# schematic.net
KiCad netlist of a schematic drawn in EasyEDA
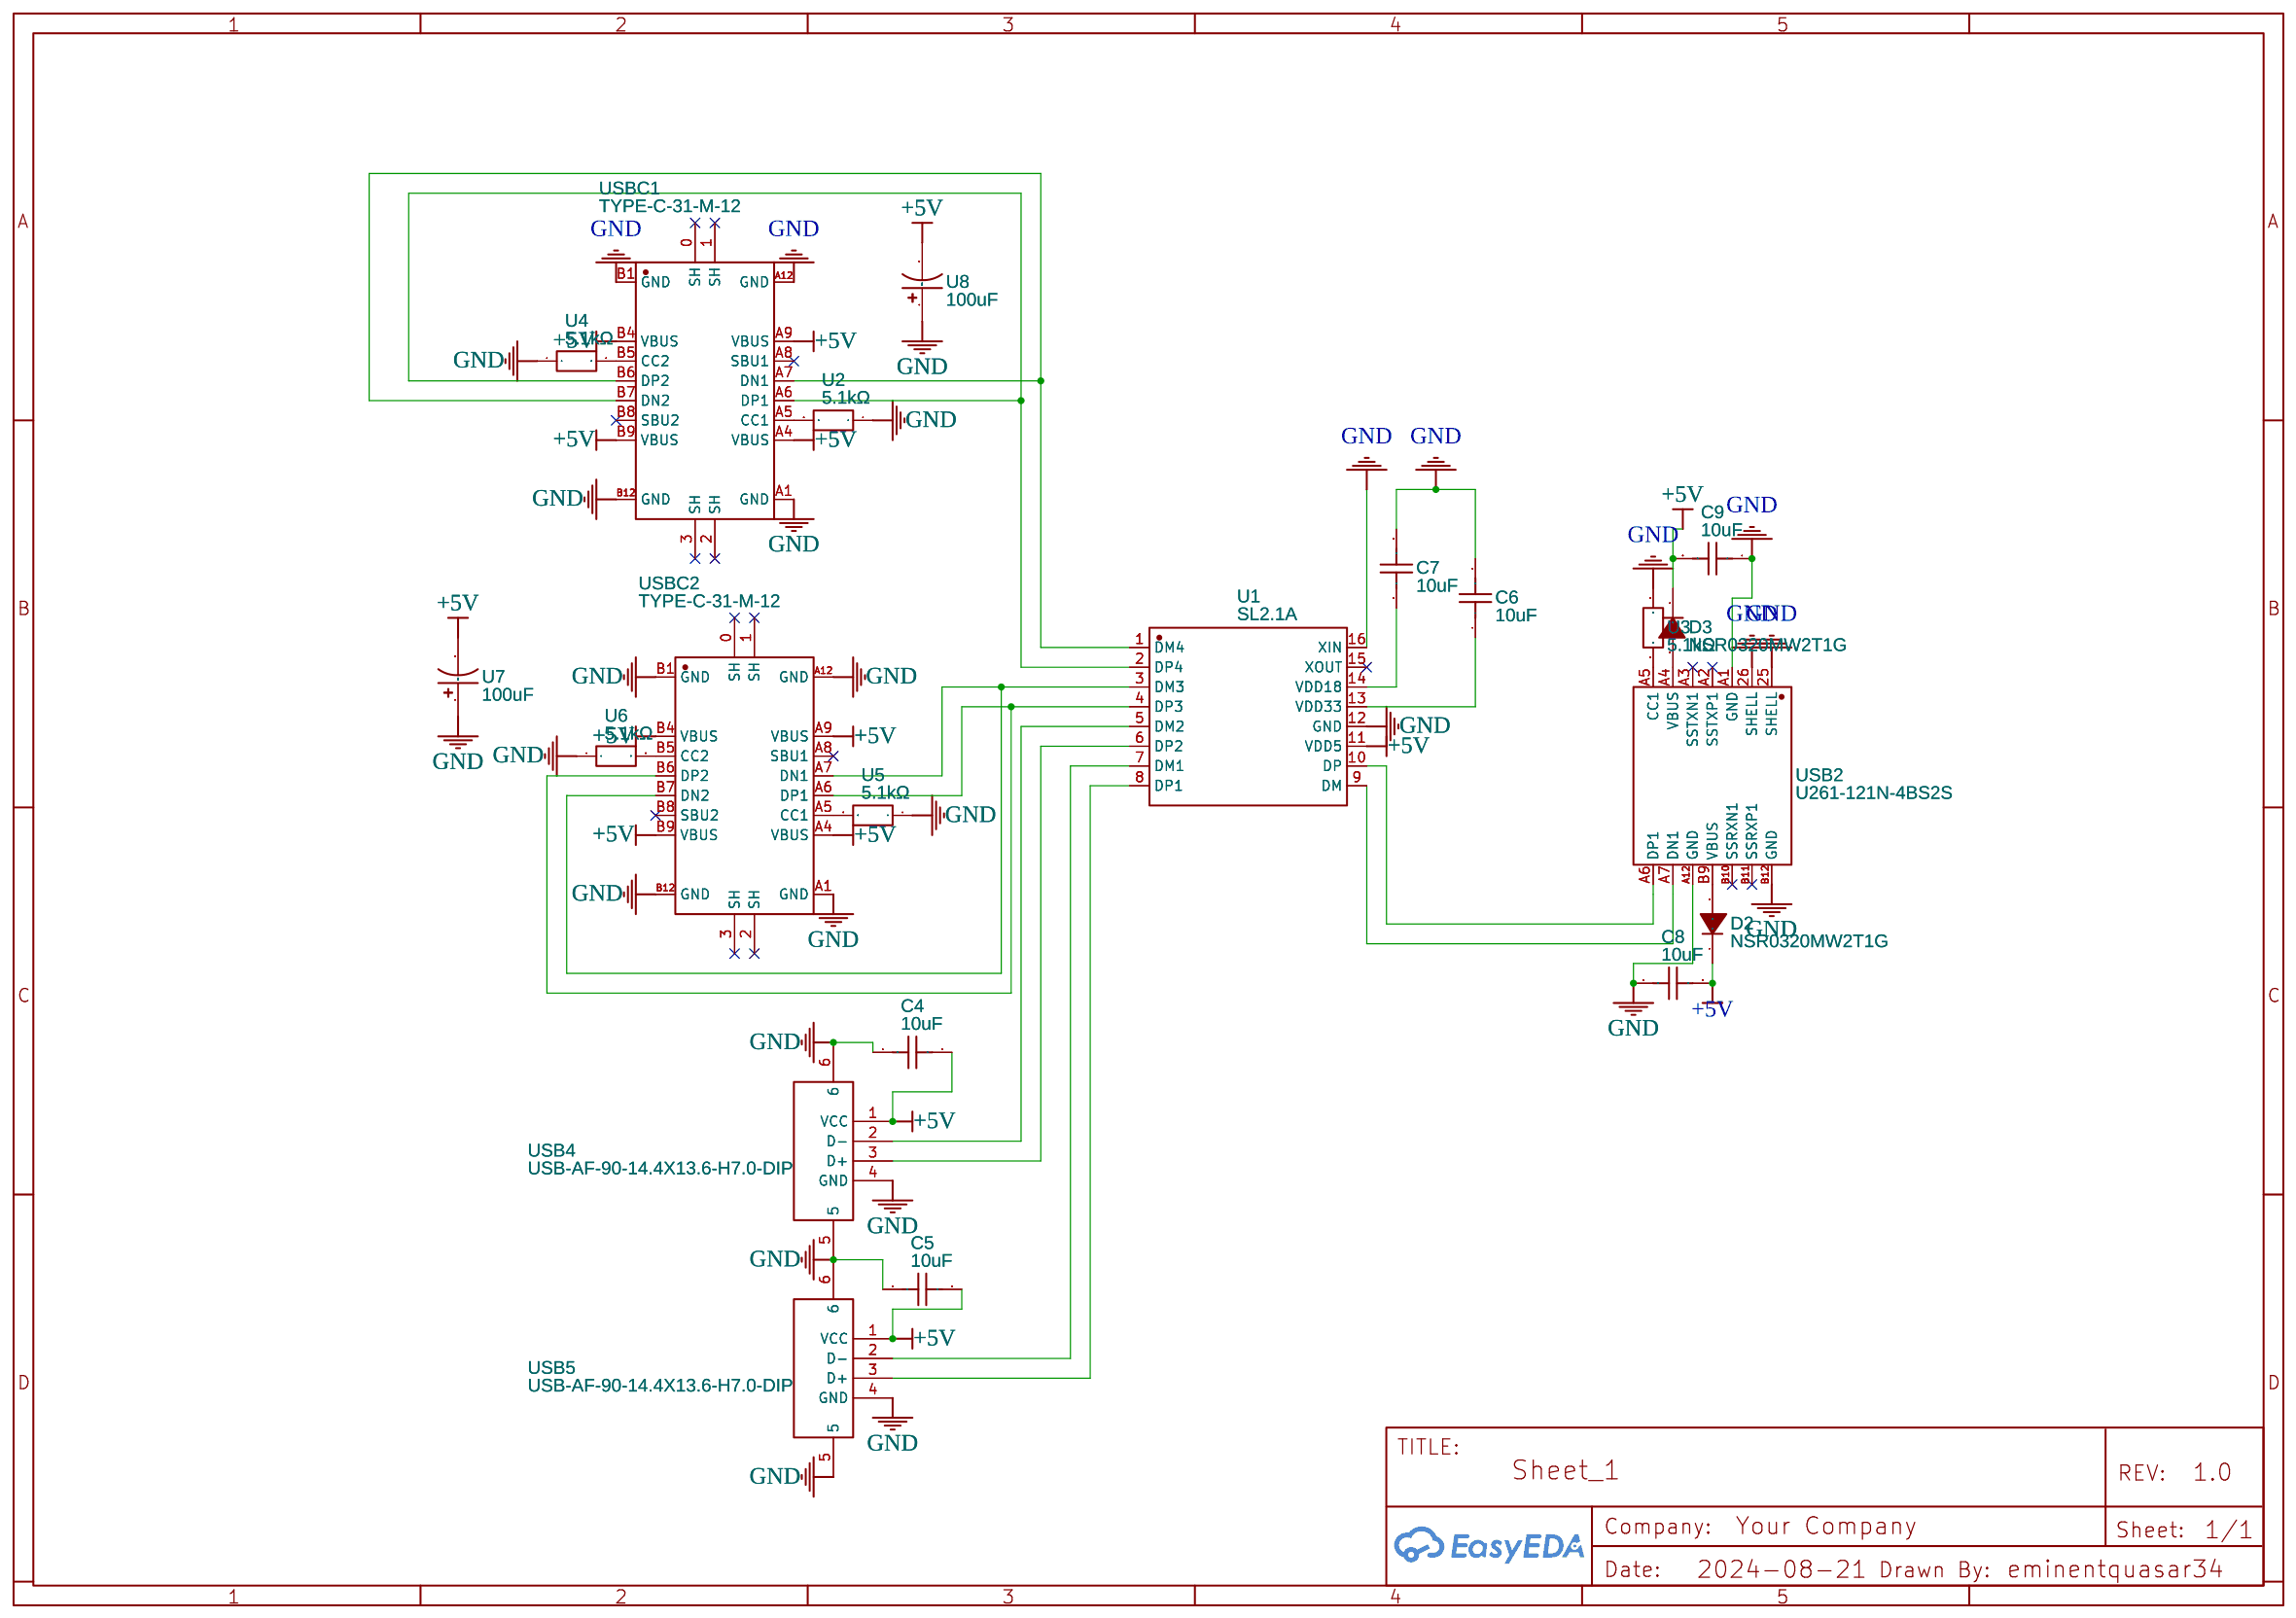
[diagram p0: schematic sheet]

(export (version "E")
  (design (tool "Eeschema 10.0.6"))
  (components
    (comp (ref "C4")
      (value "10uF")
      (fields
        (field (name "Manufacturer Part") "CL10A106KP8NNNC")
        (field (name "Manufacturer") "SAMSUNG(三星)")
      )
      (libsource (lib "") (part "CL10A106KP8NNNC"))
    )
    (comp (ref "C5")
      (value "10uF")
      (fields
        (field (name "Manufacturer Part") "CL10A106KP8NNNC")
        (field (name "Manufacturer") "SAMSUNG(三星)")
      )
      (libsource (lib "") (part "CL10A106KP8NNNC"))
    )
    (comp (ref "C6")
      (value "10uF")
      (fields
        (field (name "Manufacturer Part") "CL10A106KP8NNNC")
        (field (name "Manufacturer") "SAMSUNG(三星)")
      )
      (libsource (lib "") (part "CL10A106KP8NNNC_1"))
    )
    (comp (ref "C7")
      (value "10uF")
      (fields
        (field (name "Manufacturer Part") "CL10A106KP8NNNC")
        (field (name "Manufacturer") "SAMSUNG(三星)")
      )
      (libsource (lib "") (part "CL10A106KP8NNNC_1"))
    )
    (comp (ref "C8")
      (value "10uF")
      (fields
        (field (name "Manufacturer Part") "CL10A106KP8NNNC")
        (field (name "Manufacturer") "SAMSUNG(三星)")
      )
      (libsource (lib "") (part "CL10A106KP8NNNC"))
    )
    (comp (ref "C9")
      (value "10uF")
      (fields
        (field (name "Manufacturer Part") "CL10A106KP8NNNC")
        (field (name "Manufacturer") "SAMSUNG(三星)")
      )
      (libsource (lib "") (part "CL10A106KP8NNNC_2"))
    )
    (comp (ref "D2")
      (value "NSR0320MW2T1G")
      (fields (field (name "Manufacturer") "onsemi(安森美)"))
      (libsource (lib "") (part "NSR0320MW2T1G"))
    )
    (comp (ref "D3")
      (value "NSR0320MW2T1G")
      (fields (field (name "Manufacturer") "onsemi(安森美)"))
      (libsource (lib "") (part "NSR0320MW2T1G_1"))
    )
    (comp (ref "U1")
      (value "SL2.1A")
      (fields (field (name "Manufacturer") "CoreChips(和芯润德)"))
      (libsource (lib "") (part "SL2.1A"))
    )
    (comp (ref "U2")
      (value "5.1kΩ")
      (fields (field (name "Manufacturer Part") "CR1/4W-5K1±5%-ST26") (field (name "Manufacturer") "VO(翔胜)"))
      (libsource (lib "") (part "CR1/4W-5K1±5%-ST26"))
    )
    (comp (ref "U3")
      (value "5.1kΩ")
      (fields (field (name "Manufacturer Part") "CR1/4W-5K1±5%-ST26") (field (name "Manufacturer") "VO(翔胜)"))
      (libsource (lib "") (part "CR1/4W-5K1±5%-ST26_1"))
    )
    (comp (ref "U4")
      (value "5.1kΩ")
      (fields (field (name "Manufacturer Part") "CR1/4W-5K1±5%-ST26") (field (name "Manufacturer") "VO(翔胜)"))
      (libsource (lib "") (part "CR1/4W-5K1±5%-ST26_2"))
    )
    (comp (ref "U5")
      (value "5.1kΩ")
      (fields (field (name "Manufacturer Part") "CR1/4W-5K1±5%-ST26") (field (name "Manufacturer") "VO(翔胜)"))
      (libsource (lib "") (part "CR1/4W-5K1±5%-ST26"))
    )
    (comp (ref "U6")
      (value "5.1kΩ")
      (fields (field (name "Manufacturer Part") "CR1/4W-5K1±5%-ST26") (field (name "Manufacturer") "VO(翔胜)"))
      (libsource (lib "") (part "CR1/4W-5K1±5%-ST26_2"))
    )
    (comp (ref "U7")
      (value "100uF")
      (fields
        (field (name "Manufacturer Part") "16YXF100MEFC6.3X11")
        (field (name "Manufacturer") "rubycon(红宝石)")
      )
      (libsource (lib "") (part "16YXF100MEFC6.3X11"))
    )
    (comp (ref "U8")
      (value "100uF")
      (fields
        (field (name "Manufacturer Part") "16YXF100MEFC6.3X11")
        (field (name "Manufacturer") "rubycon(红宝石)")
      )
      (libsource (lib "") (part "16YXF100MEFC6.3X11_1"))
    )
    (comp (ref "USB2")
      (value "U261-121N-4BS2S")
      (fields (field (name "Manufacturer") "XKB Connectivity(中国星坤)"))
      (libsource (lib "") (part "U261-121N-4BS2S"))
    )
    (comp (ref "USB4")
      (value "USB-AF-90-14.4X13.6-H7.0-DIP")
      (fields (field (name "Manufacturer Part") "903-131A1011D10100") (field (name "Manufacturer") "精拓金"))
      (libsource (lib "") (part "USB-AF-90-14.4X13.6-H7.0-DIP"))
    )
    (comp (ref "USB5")
      (value "USB-AF-90-14.4X13.6-H7.0-DIP")
      (fields (field (name "Manufacturer Part") "903-131A1011D10100") (field (name "Manufacturer") "精拓金"))
      (libsource (lib "") (part "USB-AF-90-14.4X13.6-H7.0-DIP"))
    )
    (comp (ref "USBC1")
      (value "TYPE-C-31-M-12")
      (fields (field (name "Manufacturer") "韩国韩荣"))
      (libsource (lib "") (part "TYPE-C-31-M-12"))
    )
    (comp (ref "USBC2")
      (value "TYPE-C-31-M-12")
      (fields (field (name "Manufacturer") "韩国韩荣"))
      (libsource (lib "") (part "TYPE-C-31-M-12"))
    )
  )
  (nets
    (net (code "1") (name "+5V") (class "Default")
      (node (ref "C4") (pin "2") (pinfunction "2_2") (pintype "unspecified"))
      (node (ref "C5") (pin "2") (pinfunction "2_2") (pintype "unspecified"))
      (node (ref "C8") (pin "2") (pinfunction "2_2") (pintype "unspecified"))
      (node (ref "C9") (pin "2") (pinfunction "2_2") (pintype "unspecified"))
      (node (ref "D2") (pin "1") (pinfunction "C_1") (pintype "unspecified"))
      (node (ref "D3") (pin "1") (pinfunction "C_1") (pintype "unspecified"))
      (node (ref "U1") (pin "11") (pinfunction "VDD5_11") (pintype "unspecified"))
      (node (ref "U7") (pin "2") (pinfunction "2_2") (pintype "unspecified"))
      (node (ref "U8") (pin "2") (pinfunction "2_2") (pintype "unspecified"))
      (node (ref "USB4") (pin "1") (pinfunction "VCC_1") (pintype "unspecified"))
      (node (ref "USB5") (pin "1") (pinfunction "VCC_1") (pintype "unspecified"))
      (node (ref "USBC1") (pin "A4") (pinfunction "VBUS_A4") (pintype "unspecified"))
      (node (ref "USBC1") (pin "A9") (pinfunction "VBUS_A9") (pintype "unspecified"))
      (node (ref "USBC1") (pin "B4") (pinfunction "VBUS_B4") (pintype "unspecified"))
      (node (ref "USBC1") (pin "B9") (pinfunction "VBUS_B9") (pintype "unspecified"))
      (node (ref "USBC2") (pin "A4") (pinfunction "VBUS_A4") (pintype "unspecified"))
      (node (ref "USBC2") (pin "A9") (pinfunction "VBUS_A9") (pintype "unspecified"))
      (node (ref "USBC2") (pin "B4") (pinfunction "VBUS_B4") (pintype "unspecified"))
      (node (ref "USBC2") (pin "B9") (pinfunction "VBUS_B9") (pintype "unspecified"))
    )
    (net (code "2") (name "GND") (class "Default")
      (node (ref "C4") (pin "1") (pinfunction "1_1") (pintype "unspecified"))
      (node (ref "C5") (pin "1") (pinfunction "1_1") (pintype "unspecified"))
      (node (ref "C6") (pin "2") (pinfunction "2_2") (pintype "unspecified"))
      (node (ref "C7") (pin "2") (pinfunction "2_2") (pintype "unspecified"))
      (node (ref "C8") (pin "1") (pinfunction "1_1") (pintype "unspecified"))
      (node (ref "C9") (pin "1") (pinfunction "1_1") (pintype "unspecified"))
      (node (ref "U1") (pin "12") (pinfunction "GND_12") (pintype "unspecified"))
      (node (ref "U1") (pin "16") (pinfunction "XIN_16") (pintype "unspecified"))
      (node (ref "U2") (pin "1") (pinfunction "1_1") (pintype "unspecified"))
      (node (ref "U3") (pin "2") (pinfunction "2_2") (pintype "unspecified"))
      (node (ref "U4") (pin "1") (pinfunction "1_1") (pintype "unspecified"))
      (node (ref "U5") (pin "1") (pinfunction "1_1") (pintype "unspecified"))
      (node (ref "U6") (pin "1") (pinfunction "1_1") (pintype "unspecified"))
      (node (ref "U7") (pin "1") (pinfunction "1_1") (pintype "unspecified"))
      (node (ref "U8") (pin "1") (pinfunction "1_1") (pintype "unspecified"))
      (node (ref "USB2") (pin "25") (pinfunction "SHELL_25") (pintype "unspecified"))
      (node (ref "USB2") (pin "26") (pinfunction "SHELL_26") (pintype "unspecified"))
      (node (ref "USB2") (pin "A1") (pinfunction "GND_A1") (pintype "unspecified"))
      (node (ref "USB2") (pin "A12") (pinfunction "GND_A12") (pintype "unspecified"))
      (node (ref "USB2") (pin "B12") (pinfunction "GND_B12") (pintype "unspecified"))
      (node (ref "USB4") (pin "4") (pinfunction "GND_4") (pintype "unspecified"))
      (node (ref "USB4") (pin "5") (pinfunction "5_5") (pintype "unspecified"))
      (node (ref "USB4") (pin "6") (pinfunction "6_6") (pintype "unspecified"))
      (node (ref "USB5") (pin "4") (pinfunction "GND_4") (pintype "unspecified"))
      (node (ref "USB5") (pin "5") (pinfunction "5_5") (pintype "unspecified"))
      (node (ref "USB5") (pin "6") (pinfunction "6_6") (pintype "unspecified"))
      (node (ref "USBC1") (pin "A1") (pinfunction "GND_A1") (pintype "unspecified"))
      (node (ref "USBC1") (pin "A12") (pinfunction "GND_A12") (pintype "unspecified"))
      (node (ref "USBC1") (pin "B1") (pinfunction "GND_B1") (pintype "unspecified"))
      (node (ref "USBC1") (pin "B12") (pinfunction "GND_B12") (pintype "unspecified"))
      (node (ref "USBC2") (pin "A1") (pinfunction "GND_A1") (pintype "unspecified"))
      (node (ref "USBC2") (pin "A12") (pinfunction "GND_A12") (pintype "unspecified"))
      (node (ref "USBC2") (pin "B1") (pinfunction "GND_B1") (pintype "unspecified"))
      (node (ref "USBC2") (pin "B12") (pinfunction "GND_B12") (pintype "unspecified"))
    )
    (net (code "3") (name "Net-(D2-A)") (class "Default")
      (node (ref "D2") (pin "2") (pinfunction "A_2") (pintype "unspecified"))
      (node (ref "USB2") (pin "B9") (pinfunction "VBUS_B9") (pintype "unspecified"))
    )
    (net (code "4") (name "Net-(D3-A)") (class "Default")
      (node (ref "D3") (pin "2") (pinfunction "A_2") (pintype "unspecified"))
      (node (ref "USB2") (pin "A4") (pinfunction "VBUS_A4") (pintype "unspecified"))
    )
    (net (code "5") (name "Net-(U1-DM)") (class "Default")
      (node (ref "U1") (pin "9") (pinfunction "DM_9") (pintype "unspecified"))
      (node (ref "USB2") (pin "A7") (pinfunction "DN1_A7") (pintype "unspecified"))
    )
    (net (code "6") (name "Net-(U1-DM1)") (class "Default")
      (node (ref "U1") (pin "7") (pinfunction "DM1_7") (pintype "unspecified"))
      (node (ref "USB5") (pin "2") (pinfunction "D-_2") (pintype "unspecified"))
    )
    (net (code "7") (name "Net-(U1-DM2)") (class "Default")
      (node (ref "U1") (pin "5") (pinfunction "DM2_5") (pintype "unspecified"))
      (node (ref "USB4") (pin "2") (pinfunction "D-_2") (pintype "unspecified"))
    )
    (net (code "8") (name "Net-(U1-DM3)") (class "Default")
      (node (ref "U1") (pin "3") (pinfunction "DM3_3") (pintype "unspecified"))
      (node (ref "USBC2") (pin "A7") (pinfunction "DN1_A7") (pintype "unspecified"))
      (node (ref "USBC2") (pin "B7") (pinfunction "DN2_B7") (pintype "unspecified"))
    )
    (net (code "9") (name "Net-(U1-DM4)") (class "Default")
      (node (ref "U1") (pin "1") (pinfunction "DM4_1") (pintype "unspecified"))
      (node (ref "USBC1") (pin "A7") (pinfunction "DN1_A7") (pintype "unspecified"))
      (node (ref "USBC1") (pin "B7") (pinfunction "DN2_B7") (pintype "unspecified"))
    )
    (net (code "10") (name "Net-(U1-DP)") (class "Default")
      (node (ref "U1") (pin "10") (pinfunction "DP_10") (pintype "unspecified"))
      (node (ref "USB2") (pin "A6") (pinfunction "DP1_A6") (pintype "unspecified"))
    )
    (net (code "11") (name "Net-(U1-DP1)") (class "Default")
      (node (ref "U1") (pin "8") (pinfunction "DP1_8") (pintype "unspecified"))
      (node (ref "USB5") (pin "3") (pinfunction "D+_3") (pintype "unspecified"))
    )
    (net (code "12") (name "Net-(U1-DP2)") (class "Default")
      (node (ref "U1") (pin "6") (pinfunction "DP2_6") (pintype "unspecified"))
      (node (ref "USB4") (pin "3") (pinfunction "D+_3") (pintype "unspecified"))
    )
    (net (code "13") (name "Net-(U1-DP3)") (class "Default")
      (node (ref "U1") (pin "4") (pinfunction "DP3_4") (pintype "unspecified"))
      (node (ref "USBC2") (pin "A6") (pinfunction "DP1_A6") (pintype "unspecified"))
      (node (ref "USBC2") (pin "B6") (pinfunction "DP2_B6") (pintype "unspecified"))
    )
    (net (code "14") (name "Net-(U1-DP4)") (class "Default")
      (node (ref "U1") (pin "2") (pinfunction "DP4_2") (pintype "unspecified"))
      (node (ref "USBC1") (pin "A6") (pinfunction "DP1_A6") (pintype "unspecified"))
      (node (ref "USBC1") (pin "B6") (pinfunction "DP2_B6") (pintype "unspecified"))
    )
    (net (code "15") (name "Net-(U1-VDD18)") (class "Default")
      (node (ref "C7") (pin "1") (pinfunction "1_1") (pintype "unspecified"))
      (node (ref "U1") (pin "14") (pinfunction "VDD18_14") (pintype "unspecified"))
    )
    (net (code "16") (name "Net-(U1-VDD33)") (class "Default")
      (node (ref "C6") (pin "1") (pinfunction "1_1") (pintype "unspecified"))
      (node (ref "U1") (pin "13") (pinfunction "VDD33_13") (pintype "unspecified"))
    )
    (net (code "17") (name "Net-(USB2-CC1)") (class "Default")
      (node (ref "U3") (pin "1") (pinfunction "1_1") (pintype "unspecified"))
      (node (ref "USB2") (pin "A5") (pinfunction "CC1_A5") (pintype "unspecified"))
    )
    (net (code "18") (name "Net-(USBC1-CC1)") (class "Default")
      (node (ref "U2") (pin "2") (pinfunction "2_2") (pintype "unspecified"))
      (node (ref "USBC1") (pin "A5") (pinfunction "CC1_A5") (pintype "unspecified"))
    )
    (net (code "19") (name "Net-(USBC1-CC2)") (class "Default")
      (node (ref "U4") (pin "2") (pinfunction "2_2") (pintype "unspecified"))
      (node (ref "USBC1") (pin "B5") (pinfunction "CC2_B5") (pintype "unspecified"))
    )
    (net (code "20") (name "Net-(USBC2-CC1)") (class "Default")
      (node (ref "U5") (pin "2") (pinfunction "2_2") (pintype "unspecified"))
      (node (ref "USBC2") (pin "A5") (pinfunction "CC1_A5") (pintype "unspecified"))
    )
    (net (code "21") (name "Net-(USBC2-CC2)") (class "Default")
      (node (ref "U6") (pin "2") (pinfunction "2_2") (pintype "unspecified"))
      (node (ref "USBC2") (pin "B5") (pinfunction "CC2_B5") (pintype "unspecified"))
    )
    (net (code "22") (name "unconnected-(U1-XOUT-Pad15)") (class "Default")
      (node (ref "U1") (pin "15") (pinfunction "XOUT_15") (pintype "unspecified+no_connect"))
    )
    (net (code "23") (name "unconnected-(USB2-SSRXN1-PadB10)") (class "Default")
      (node (ref "USB2") (pin "B10") (pinfunction "SSRXN1_B10") (pintype "unspecified+no_connect"))
    )
    (net (code "24") (name "unconnected-(USB2-SSRXP1-PadB11)") (class "Default")
      (node (ref "USB2") (pin "B11") (pinfunction "SSRXP1_B11") (pintype "unspecified+no_connect"))
    )
    (net (code "25") (name "unconnected-(USB2-SSTXN1-PadA3)") (class "Default")
      (node (ref "USB2") (pin "A3") (pinfunction "SSTXN1_A3") (pintype "unspecified+no_connect"))
    )
    (net (code "26") (name "unconnected-(USB2-SSTXP1-PadA2)") (class "Default")
      (node (ref "USB2") (pin "A2") (pinfunction "SSTXP1_A2") (pintype "unspecified+no_connect"))
    )
    (net (code "27") (name "unconnected-(USBC1-SBU1-PadA8)") (class "Default")
      (node (ref "USBC1") (pin "A8") (pinfunction "SBU1_A8") (pintype "unspecified+no_connect"))
    )
    (net (code "28") (name "unconnected-(USBC1-SBU2-PadB8)") (class "Default")
      (node (ref "USBC1") (pin "B8") (pinfunction "SBU2_B8") (pintype "unspecified+no_connect"))
    )
    (net (code "29") (name "unconnected-(USBC1-SH-Pad0)") (class "Default")
      (node (ref "USBC1") (pin "0") (pinfunction "SH_0") (pintype "unspecified+no_connect"))
    )
    (net (code "30") (name "unconnected-(USBC1-SH-Pad1)") (class "Default")
      (node (ref "USBC1") (pin "1") (pinfunction "SH_1") (pintype "unspecified+no_connect"))
    )
    (net (code "31") (name "unconnected-(USBC1-SH-Pad2)") (class "Default")
      (node (ref "USBC1") (pin "2") (pinfunction "SH_2") (pintype "unspecified+no_connect"))
    )
    (net (code "32") (name "unconnected-(USBC1-SH-Pad3)") (class "Default")
      (node (ref "USBC1") (pin "3") (pinfunction "SH_3") (pintype "unspecified+no_connect"))
    )
    (net (code "33") (name "unconnected-(USBC2-SBU1-PadA8)") (class "Default")
      (node (ref "USBC2") (pin "A8") (pinfunction "SBU1_A8") (pintype "unspecified+no_connect"))
    )
    (net (code "34") (name "unconnected-(USBC2-SBU2-PadB8)") (class "Default")
      (node (ref "USBC2") (pin "B8") (pinfunction "SBU2_B8") (pintype "unspecified+no_connect"))
    )
    (net (code "35") (name "unconnected-(USBC2-SH-Pad0)") (class "Default")
      (node (ref "USBC2") (pin "0") (pinfunction "SH_0") (pintype "unspecified+no_connect"))
    )
    (net (code "36") (name "unconnected-(USBC2-SH-Pad1)") (class "Default")
      (node (ref "USBC2") (pin "1") (pinfunction "SH_1") (pintype "unspecified+no_connect"))
    )
    (net (code "37") (name "unconnected-(USBC2-SH-Pad2)") (class "Default")
      (node (ref "USBC2") (pin "2") (pinfunction "SH_2") (pintype "unspecified+no_connect"))
    )
    (net (code "38") (name "unconnected-(USBC2-SH-Pad3)") (class "Default")
      (node (ref "USBC2") (pin "3") (pinfunction "SH_3") (pintype "unspecified+no_connect"))
    )
  )
)
